# Alimentation.net
KiCad netlist of a schematic drawn in Altium Designer
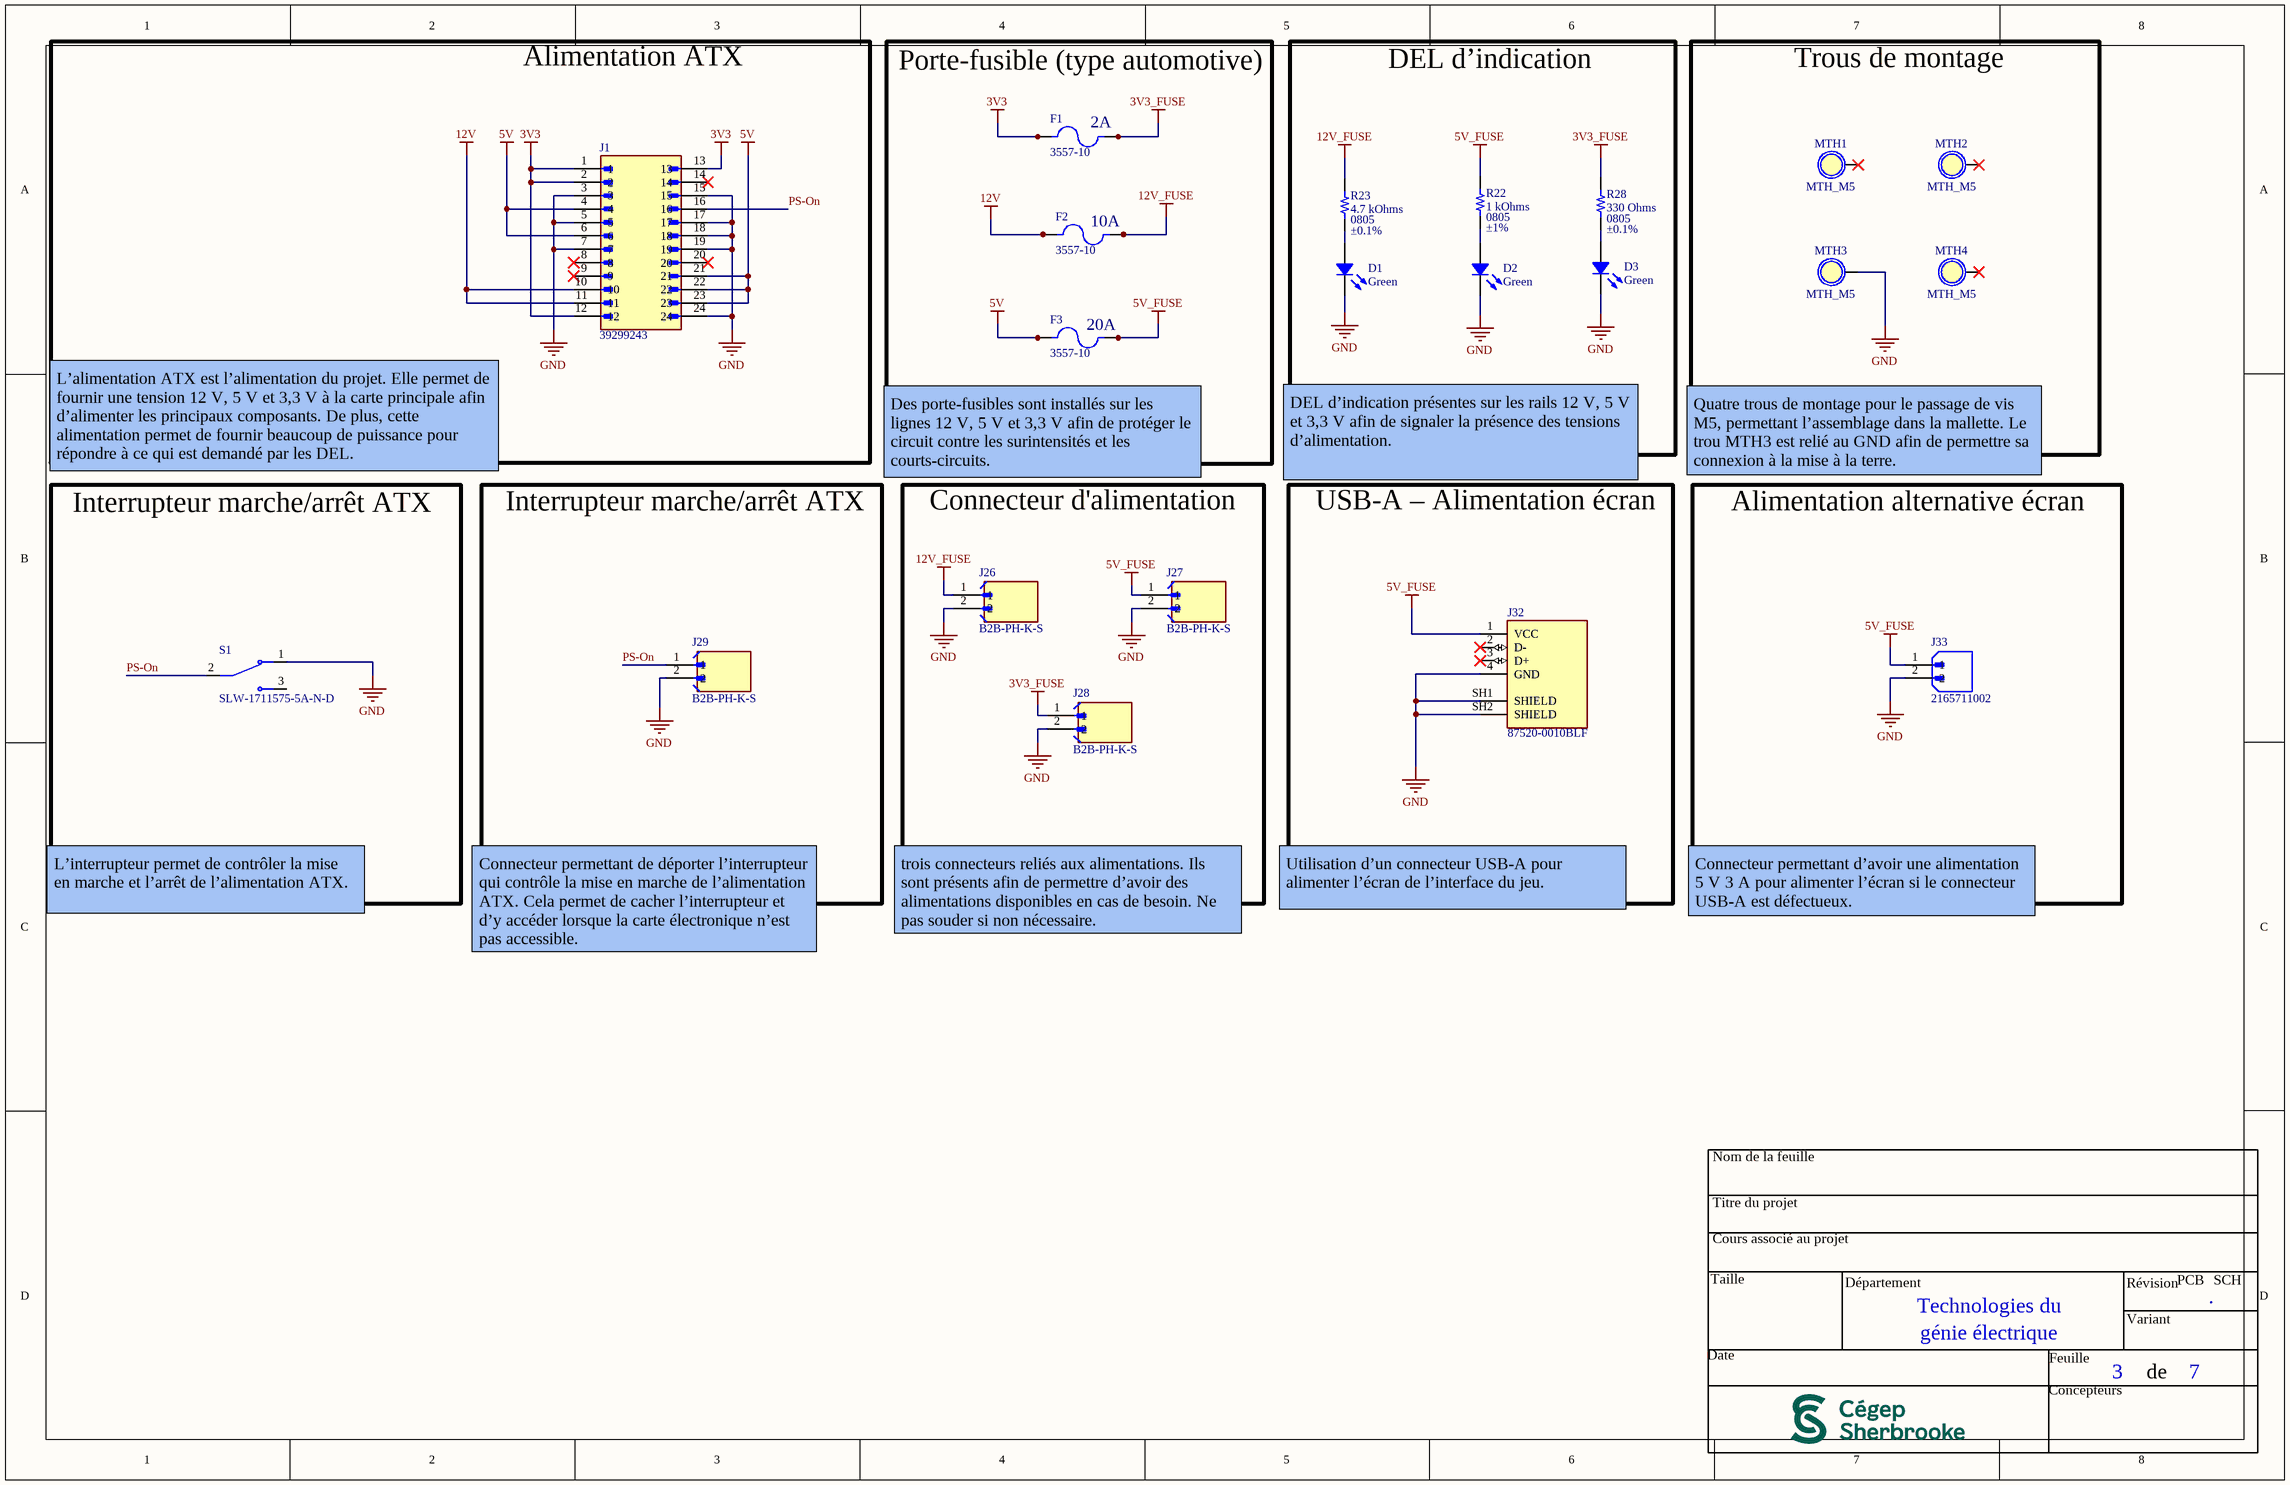
[diagram p0: Alimentation.SchDoc]

(export (version "E")
  (design (tool "Eeschema 10.0.6"))
  (components
    (comp (ref "D1")
      (value "Green")
      (footprint "LED 0805_2012 GREEN")
      (description "LED GREEN 0805 SMD")
      (fields (field (name "PART NUMBER") "5975316507F") (field (name "MANUFACTURER") "Dialight"))
      (libsource (lib "Celestial Altium Library - altium_library") (part "LED"))
    )
    (comp (ref "D2")
      (value "Green")
      (footprint "LED 0805_2012 GREEN")
      (description "LED GREEN 0805 SMD")
      (fields (field (name "PART NUMBER") "5975316507F") (field (name "MANUFACTURER") "Dialight"))
      (libsource (lib "Celestial Altium Library - altium_library") (part "LED"))
    )
    (comp (ref "D3")
      (value "Green")
      (footprint "LED 0805_2012 GREEN")
      (description "LED GREEN 0805 SMD")
      (fields (field (name "PART NUMBER") "5975316507F") (field (name "MANUFACTURER") "Dialight"))
      (libsource (lib "Celestial Altium Library - altium_library") (part "LED"))
    )
    (comp (ref "F1")
      (value "3557-10")
      (footprint "FUSE_3557-10")
      (fields (field (name "MF") "Keystone"))
      (libsource (lib "3557-10") (part "3557-10"))
    )
    (comp (ref "F2")
      (value "3557-10")
      (footprint "FUSE_3557-10")
      (fields (field (name "MF") "Keystone"))
      (libsource (lib "3557-10") (part "3557-10"))
    )
    (comp (ref "F3")
      (value "3557-10")
      (footprint "FUSE_3557-10")
      (fields (field (name "MF") "Keystone"))
      (libsource (lib "3557-10") (part "3557-10"))
    )
    (comp (ref "J1")
      (value "39299243")
      (footprint "MOLEX_39299243")
      (description "Conn Wire to Board HDR 24Power POS 4.2mm Solder ST Top Entry Thru-Hole Tray")
      (libsource (lib "39299243") (part "39299243"))
    )
    (comp (ref "J26")
      (value "B2B-PH-K-S")
      (footprint "JST_B2B-PH-K-S")
      (description "Connector Header Through Hole 2 position 0.079 (2.00mm)")
      (fields (field (name "MF") "JST Sales America Inc."))
      (libsource (lib "B2B-PH-K-S") (part "B2B-PH-K-S"))
    )
    (comp (ref "J27")
      (value "B2B-PH-K-S")
      (footprint "JST_B2B-PH-K-S")
      (description "Connector Header Through Hole 2 position 0.079 (2.00mm)")
      (fields (field (name "MF") "JST Sales America Inc."))
      (libsource (lib "B2B-PH-K-S") (part "B2B-PH-K-S"))
    )
    (comp (ref "J28")
      (value "B2B-PH-K-S")
      (footprint "JST_B2B-PH-K-S")
      (description "Connector Header Through Hole 2 position 0.079 (2.00mm)")
      (fields (field (name "MF") "JST Sales America Inc."))
      (libsource (lib "B2B-PH-K-S") (part "B2B-PH-K-S"))
    )
    (comp (ref "J29")
      (value "B2B-PH-K-S")
      (footprint "JST_B2B-PH-K-S")
      (description "Connector Header Through Hole 2 position 0.079 (2.00mm)")
      (fields (field (name "MF") "JST Sales America Inc."))
      (libsource (lib "B2B-PH-K-S") (part "B2B-PH-K-S"))
    )
    (comp (ref "J32")
      (value "87520-0010BLF")
      (footprint "AMPHENOL_87520-0010BLF")
      (fields (field (name "MF") "AMPHENOL ICC / FCI"))
      (libsource (lib "87520-0010BLF") (part "87520-0010BLF"))
    )
    (comp (ref "J33")
      (value "2165711002")
      (footprint "MOLEX_2165711002")
      (libsource (lib "2165711002") (part "2165711002"))
    )
    (comp (ref "MTH1")
      (value "MTH_M5")
      (footprint "MTH_M5")
      (description "MTH - MOUNTING HOLE 5MM PLATED - 5MM")
      (fields (field (name "SOURCE") "CEGEP_SHERBROOKE_TGE_LIBRARY.SchLib"))
      (libsource (lib "Cegep de Sherbrooke") (part "MTH_M3.5_PLATED"))
    )
    (comp (ref "MTH2")
      (value "MTH_M5")
      (footprint "MTH_M5")
      (description "MTH - MOUNTING HOLE 5MM PLATED - 5MM")
      (fields (field (name "SOURCE") "CEGEP_SHERBROOKE_TGE_LIBRARY.SchLib"))
      (libsource (lib "Cegep de Sherbrooke") (part "MTH_M3.5_PLATED"))
    )
    (comp (ref "MTH3")
      (value "MTH_M5")
      (footprint "MTH_M5")
      (description "MTH - MOUNTING HOLE 5MM PLATED - 5MM")
      (fields (field (name "SOURCE") "CEGEP_SHERBROOKE_TGE_LIBRARY.SchLib"))
      (libsource (lib "Cegep de Sherbrooke") (part "MTH_M3.5_PLATED"))
    )
    (comp (ref "MTH4")
      (value "MTH_M5")
      (footprint "MTH_M5")
      (description "MTH - MOUNTING HOLE 5MM PLATED - 5MM")
      (fields (field (name "SOURCE") "CEGEP_SHERBROOKE_TGE_LIBRARY.SchLib"))
      (libsource (lib "Cegep de Sherbrooke") (part "MTH_M3.5_PLATED"))
    )
    (comp (ref "R22")
      (value "1 kOhms")
      (footprint "RES 0805_2012")
      (description "RES 1K OHM 1% 1/4W 0805")
      (fields
        (field (name "PART NUMBER") "RNCP0805FTD1K00")
        (field (name "MANUFACTURER") "Stackpole Electronics Inc")
        (field (name "SUPPLIER DEVICE PACKAGE") "0805")
        (field (name "TOLERANCE") "±1%")
      )
      (libsource (lib "Celestial Altium Library - altium_library") (part "Resistor"))
    )
    (comp (ref "R23")
      (value "4.7 kOhms")
      (footprint "RES 0805_2012")
      (description "RES SMD 4.7K OHM 0.1% 1/4W 0805")
      (fields
        (field (name "PART NUMBER") "ERJ-PB6B4701V")
        (field (name "MANUFACTURER") "Panasonic Electronic Components")
        (field (name "SUPPLIER DEVICE PACKAGE") "0805")
        (field (name "TOLERANCE") "±0.1%")
      )
      (libsource (lib "Celestial Altium Library - altium_library") (part "Resistor"))
    )
    (comp (ref "R28")
      (value "330 Ohms")
      (footprint "RES 0805_2012")
      (description "RES SMD 330 OHM 0.1% 1/4W 0805")
      (fields
        (field (name "PART NUMBER") "ERJ-PB6B3300V")
        (field (name "MANUFACTURER") "Panasonic Electronic Components")
        (field (name "SUPPLIER DEVICE PACKAGE") "0805")
        (field (name "TOLERANCE") "±0.1%")
      )
      (libsource (lib "Celestial Altium Library - altium_library") (part "Resistor"))
    )
    (comp (ref "S1")
      (value "SLW-1711575-5A-N-D")
      (footprint "SW_SLW-1711575-5A-N-D")
      (description "Switch Slide ON ON SPDT Raised Slide 0.3A 50VDC 10000Cycles PC Pins Thru-Hole")
      (fields (field (name "MF") "Same Sky"))
      (libsource (lib "SLW-1711575-5A-N-D") (part "SLW-1711575-5A-N-D"))
    )
  )
  (nets
    (net (code "1") (name "/PS-On") (class "Default")
      (node (ref "J1") (pin "16") (pinfunction "16_16") (pintype "passive"))
      (node (ref "J29") (pin "1") (pinfunction "1_1") (pintype "passive"))
      (node (ref "S1") (pin "2") (pinfunction "2_2") (pintype "passive"))
    )
    (net (code "2") (name "3V3") (class "Default")
      (node (ref "F1") (pin "1_1") (pinfunction "1_1_1") (pintype "passive"))
      (node (ref "F1") (pin "1_2") (pinfunction "1_1_2") (pintype "passive"))
      (node (ref "J1") (pin "1") (pinfunction "1_1") (pintype "passive"))
      (node (ref "J1") (pin "12") (pinfunction "12_12") (pintype "passive"))
      (node (ref "J1") (pin "13") (pinfunction "13_13") (pintype "passive"))
      (node (ref "J1") (pin "2") (pinfunction "2_2") (pintype "passive"))
    )
    (net (code "3") (name "3V3_FUSE") (class "Default")
      (node (ref "F1") (pin "2_1") (pinfunction "2_2_1") (pintype "passive"))
      (node (ref "F1") (pin "2_2") (pinfunction "2_2_2") (pintype "passive"))
      (node (ref "J28") (pin "1") (pinfunction "1_1") (pintype "passive"))
      (node (ref "R28") (pin "2") (pinfunction "2_2") (pintype "passive"))
    )
    (net (code "4") (name "5V") (class "Default")
      (node (ref "F3") (pin "1_1") (pinfunction "1_1_1") (pintype "passive"))
      (node (ref "F3") (pin "1_2") (pinfunction "1_1_2") (pintype "passive"))
      (node (ref "J1") (pin "21") (pinfunction "21_21") (pintype "passive"))
      (node (ref "J1") (pin "22") (pinfunction "22_22") (pintype "passive"))
      (node (ref "J1") (pin "23") (pinfunction "23_23") (pintype "passive"))
      (node (ref "J1") (pin "4") (pinfunction "4_4") (pintype "passive"))
      (node (ref "J1") (pin "6") (pinfunction "6_6") (pintype "passive"))
    )
    (net (code "5") (name "5V_FUSE") (class "Default")
      (node (ref "F3") (pin "2_1") (pinfunction "2_2_1") (pintype "passive"))
      (node (ref "F3") (pin "2_2") (pinfunction "2_2_2") (pintype "passive"))
      (node (ref "J27") (pin "1") (pinfunction "1_1") (pintype "passive"))
      (node (ref "J32") (pin "1") (pinfunction "VCC_1") (pintype "power_in"))
      (node (ref "J33") (pin "1") (pinfunction "1_1") (pintype "passive"))
      (node (ref "R22") (pin "2") (pinfunction "2_2") (pintype "passive"))
    )
    (net (code "6") (name "12V") (class "Default")
      (node (ref "F2") (pin "1_1") (pinfunction "1_1_1") (pintype "passive"))
      (node (ref "F2") (pin "1_2") (pinfunction "1_1_2") (pintype "passive"))
      (node (ref "J1") (pin "10") (pinfunction "10_10") (pintype "passive"))
      (node (ref "J1") (pin "11") (pinfunction "11_11") (pintype "passive"))
    )
    (net (code "7") (name "12V_FUSE") (class "Default")
      (node (ref "F2") (pin "2_1") (pinfunction "2_2_1") (pintype "passive"))
      (node (ref "F2") (pin "2_2") (pinfunction "2_2_2") (pintype "passive"))
      (node (ref "J26") (pin "1") (pinfunction "1_1") (pintype "passive"))
      (node (ref "R23") (pin "2") (pinfunction "2_2") (pintype "passive"))
    )
    (net (code "8") (name "GND") (class "Default")
      (node (ref "D1") (pin "2") (pinfunction "2_2") (pintype "passive"))
      (node (ref "D2") (pin "2") (pinfunction "2_2") (pintype "passive"))
      (node (ref "D3") (pin "2") (pinfunction "2_2") (pintype "passive"))
      (node (ref "J1") (pin "15") (pinfunction "15_15") (pintype "passive"))
      (node (ref "J1") (pin "17") (pinfunction "17_17") (pintype "passive"))
      (node (ref "J1") (pin "18") (pinfunction "18_18") (pintype "passive"))
      (node (ref "J1") (pin "19") (pinfunction "19_19") (pintype "passive"))
      (node (ref "J1") (pin "24") (pinfunction "24_24") (pintype "passive"))
      (node (ref "J1") (pin "3") (pinfunction "3_3") (pintype "passive"))
      (node (ref "J1") (pin "5") (pinfunction "5_5") (pintype "passive"))
      (node (ref "J1") (pin "7") (pinfunction "7_7") (pintype "passive"))
      (node (ref "J26") (pin "2") (pinfunction "2_2") (pintype "passive"))
      (node (ref "J27") (pin "2") (pinfunction "2_2") (pintype "passive"))
      (node (ref "J28") (pin "2") (pinfunction "2_2") (pintype "passive"))
      (node (ref "J29") (pin "2") (pinfunction "2_2") (pintype "passive"))
      (node (ref "J32") (pin "4") (pinfunction "GND_4") (pintype "power_in"))
      (node (ref "J32") (pin "SH1") (pinfunction "SHIELD_SH1") (pintype "passive"))
      (node (ref "J32") (pin "SH2") (pinfunction "SHIELD_SH2") (pintype "passive"))
      (node (ref "J33") (pin "2") (pinfunction "2_2") (pintype "passive"))
      (node (ref "MTH3") (pin "1") (pinfunction "1_1") (pintype "passive"))
      (node (ref "S1") (pin "1") (pinfunction "1_1") (pintype "passive"))
    )
    (net (code "9") (name "Net-(D1-Pad1)") (class "Default")
      (node (ref "D1") (pin "1") (pinfunction "1_1") (pintype "passive"))
      (node (ref "R23") (pin "1") (pinfunction "1_1") (pintype "passive"))
    )
    (net (code "10") (name "Net-(D2-Pad1)") (class "Default")
      (node (ref "D2") (pin "1") (pinfunction "1_1") (pintype "passive"))
      (node (ref "R22") (pin "1") (pinfunction "1_1") (pintype "passive"))
    )
    (net (code "11") (name "Net-(D3-Pad1)") (class "Default")
      (node (ref "D3") (pin "1") (pinfunction "1_1") (pintype "passive"))
      (node (ref "R28") (pin "1") (pinfunction "1_1") (pintype "passive"))
    )
    (net (code "12") (name "unconnected-(J1-Pad8)") (class "Default")
      (node (ref "J1") (pin "8") (pinfunction "8_8") (pintype "passive+no_connect"))
    )
    (net (code "13") (name "unconnected-(J1-Pad9)") (class "Default")
      (node (ref "J1") (pin "9") (pinfunction "9_9") (pintype "passive+no_connect"))
    )
    (net (code "14") (name "unconnected-(J1-Pad14)") (class "Default")
      (node (ref "J1") (pin "14") (pinfunction "14_14") (pintype "passive+no_connect"))
    )
    (net (code "15") (name "unconnected-(J1-Pad20)") (class "Default")
      (node (ref "J1") (pin "20") (pinfunction "20_20") (pintype "passive+no_connect"))
    )
    (net (code "16") (name "unconnected-(J32-D+-Pad3)") (class "Default")
      (node (ref "J32") (pin "3") (pinfunction "D+_3") (pintype "bidirectional+no_connect"))
    )
    (net (code "17") (name "unconnected-(J32-D--Pad2)") (class "Default")
      (node (ref "J32") (pin "2") (pinfunction "D-_2") (pintype "bidirectional+no_connect"))
    )
    (net (code "18") (name "unconnected-(MTH1-Pad1)") (class "Default")
      (node (ref "MTH1") (pin "1") (pinfunction "1_1") (pintype "passive+no_connect"))
    )
    (net (code "19") (name "unconnected-(MTH2-Pad1)") (class "Default")
      (node (ref "MTH2") (pin "1") (pinfunction "1_1") (pintype "passive+no_connect"))
    )
    (net (code "20") (name "unconnected-(MTH4-Pad1)") (class "Default")
      (node (ref "MTH4") (pin "1") (pinfunction "1_1") (pintype "passive+no_connect"))
    )
    (net (code "21") (name "unconnected-(S1-Pad3)") (class "Default")
      (node (ref "S1") (pin "3") (pinfunction "3_3") (pintype "passive"))
    )
  )
)
